# Schematic_16bitCalculator.net
KiCad netlist of a schematic drawn in EasyEDA
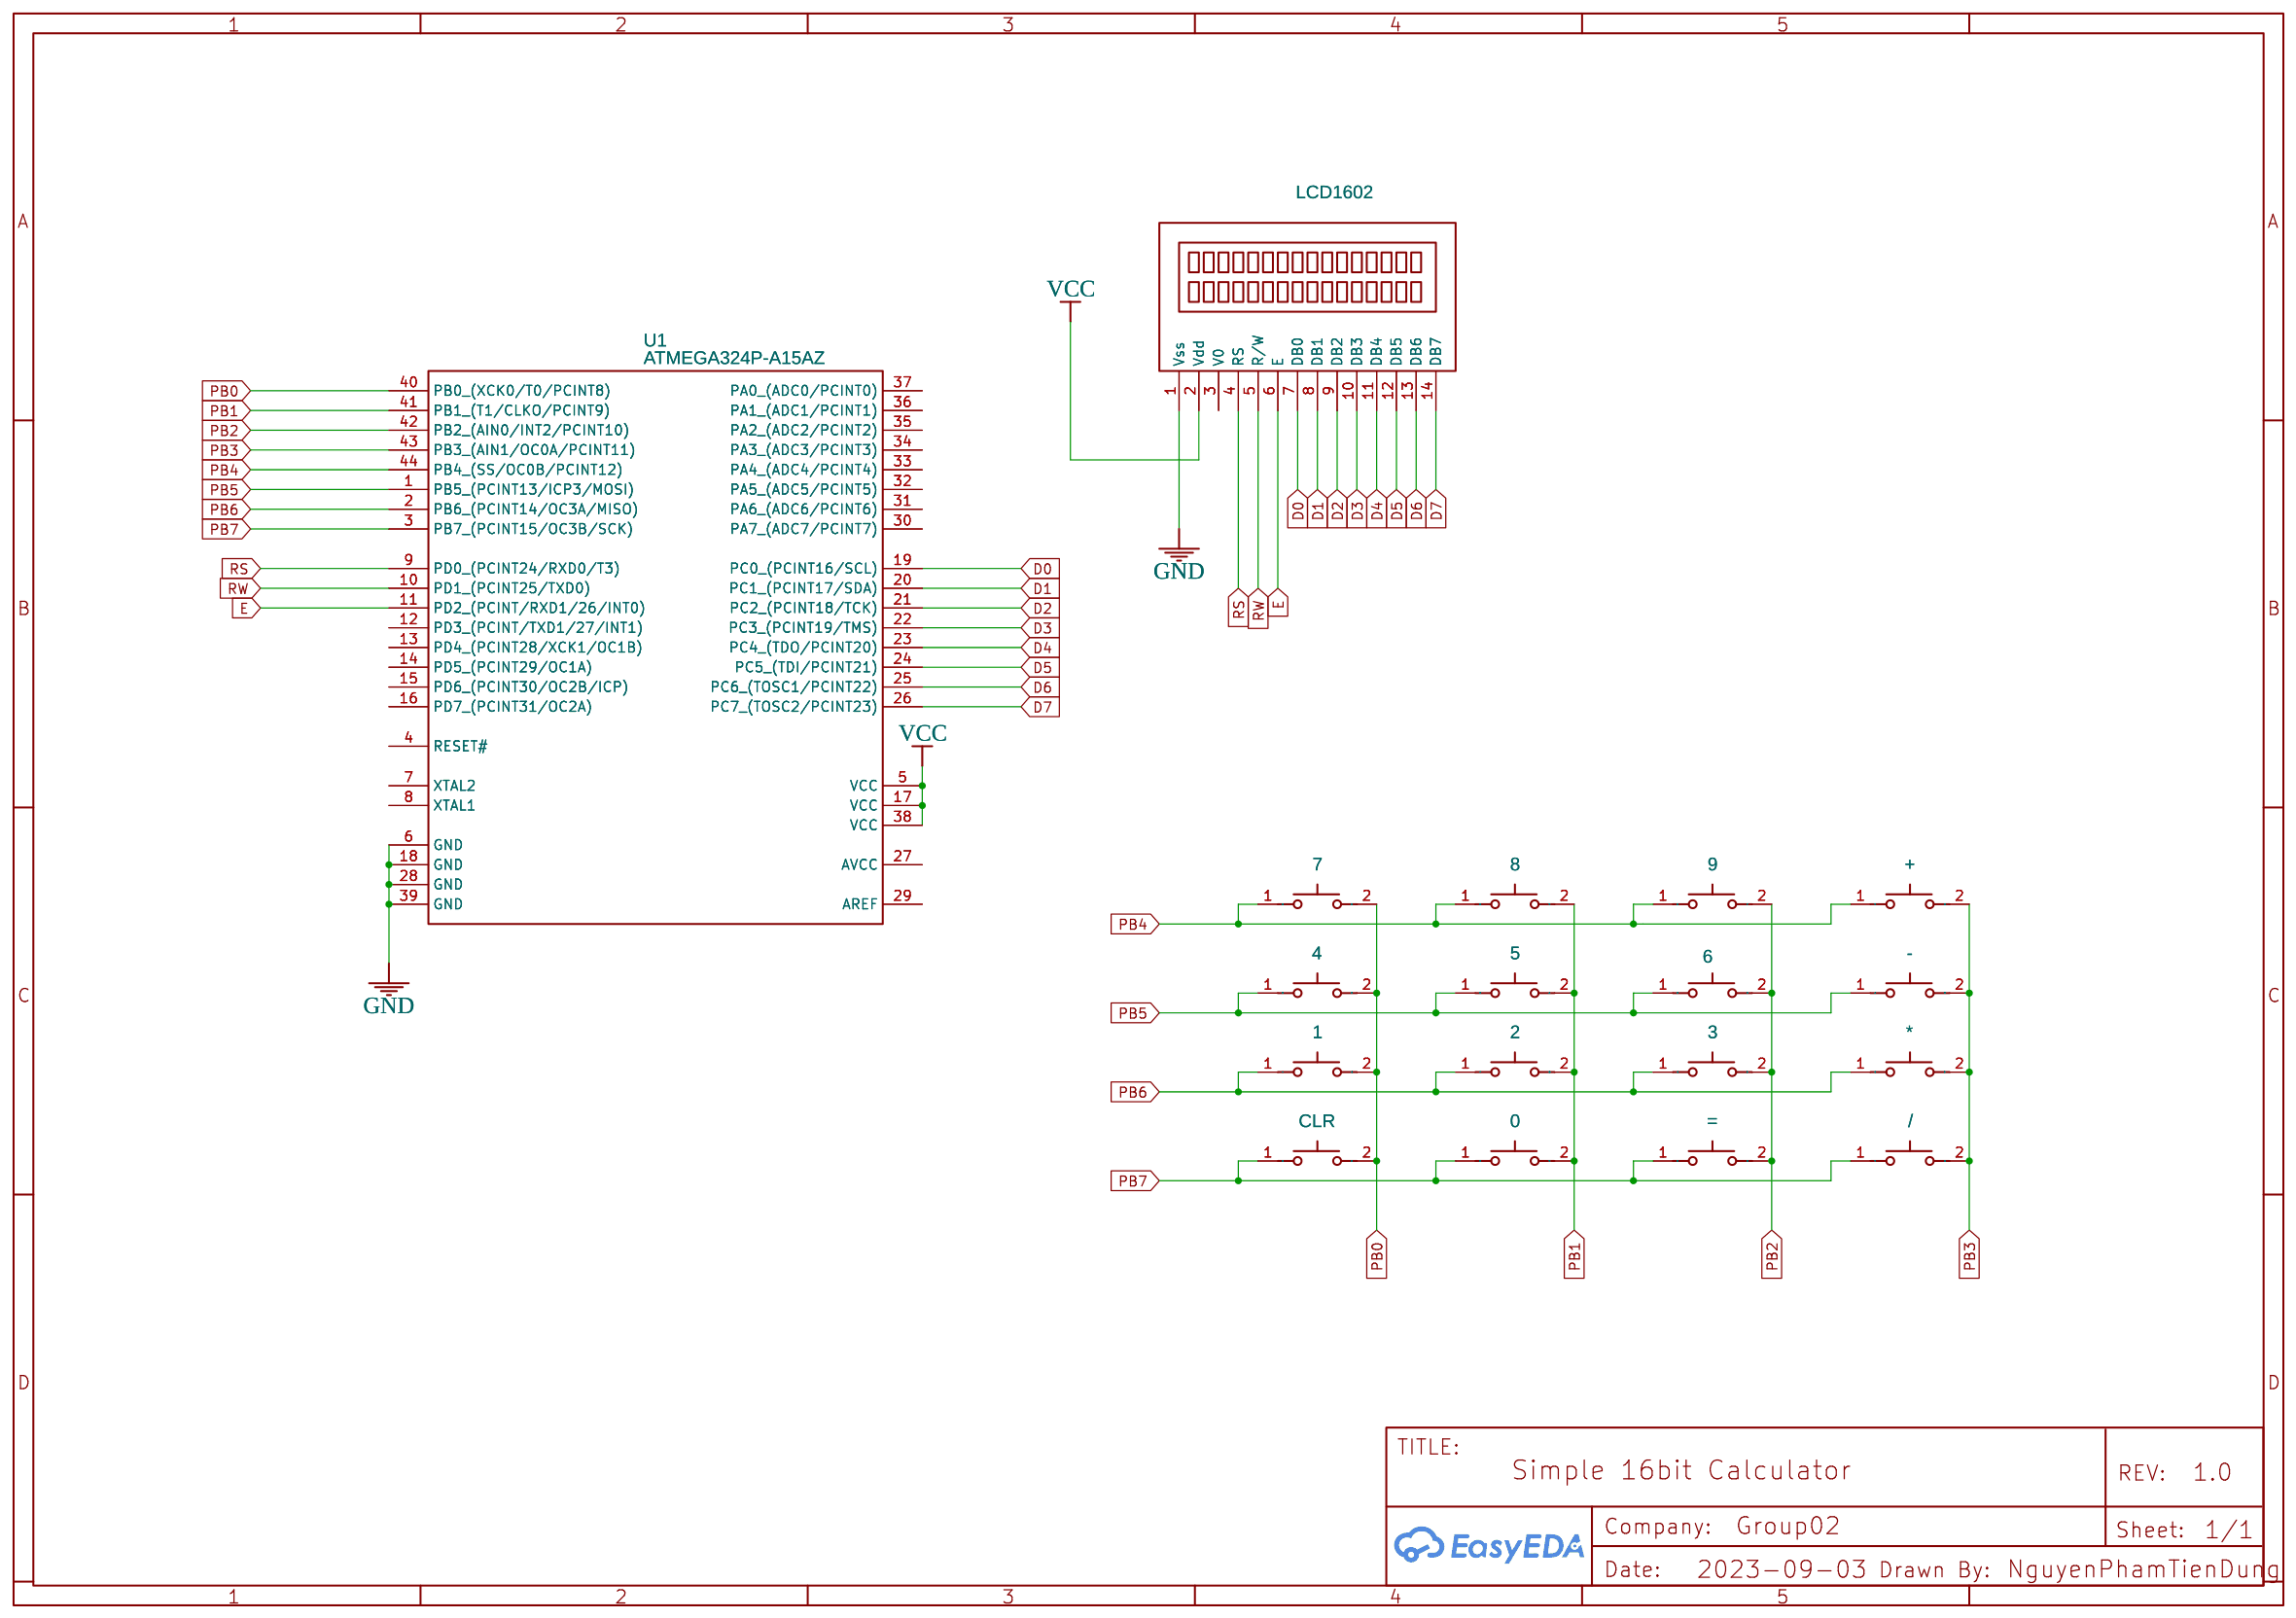
[diagram p0: schematic sheet]

(export (version "E")
  (design (tool "Eeschema 10.0.6"))
  (components
    (comp (ref "*") (value "BUTTON2") (libsource (lib "") (part "BUTTON2_5")))
    (comp (ref "+") (value "BUTTON2") (libsource (lib "") (part "BUTTON2_3")))
    (comp (ref "-") (value "BUTTON2") (libsource (lib "") (part "BUTTON2_6")))
    (comp (ref "/") (value "BUTTON2") (libsource (lib "") (part "BUTTON2_1")))
    (comp (ref "0") (value "BUTTON2") (libsource (lib "") (part "BUTTON2")))
    (comp (ref "1") (value "BUTTON2") (libsource (lib "") (part "BUTTON2")))
    (comp (ref "2") (value "BUTTON2") (libsource (lib "") (part "BUTTON2")))
    (comp (ref "3") (value "BUTTON2") (libsource (lib "") (part "BUTTON2")))
    (comp (ref "4") (value "BUTTON2") (libsource (lib "") (part "BUTTON2")))
    (comp (ref "5") (value "BUTTON2") (libsource (lib "") (part "BUTTON2")))
    (comp (ref "6") (value "BUTTON2") (libsource (lib "") (part "BUTTON2")))
    (comp (ref "7") (value "BUTTON2") (libsource (lib "") (part "BUTTON2")))
    (comp (ref "8") (value "BUTTON2") (libsource (lib "") (part "BUTTON2")))
    (comp (ref "9") (value "BUTTON2") (libsource (lib "") (part "BUTTON2")))
    (comp (ref "=") (value "BUTTON2") (libsource (lib "") (part "BUTTON2_2")))
    (comp (ref "CLR") (value "BUTTON2") (libsource (lib "") (part "BUTTON2_4")))
    (comp (ref "LCD1602")
      (value "NO")
      (fields (field (name "Manufacturer Part") "LCD LM016L 16x2"))
      (libsource (lib "") (part "LM016L"))
    )
    (comp (ref "U1")
      (value "ATMEGA324P-A15AZ")
      (fields (field (name "Manufacturer") "Atmel"))
      (libsource (lib "") (part "ATMEGA324P-A15AZ"))
    )
  )
  (nets
    (net (code "1") (name "D0") (class "Default")
      (node (ref "LCD1602") (pin "7") (pinfunction "DB0_7") (pintype "unspecified"))
      (node (ref "U1") (pin "19") (pinfunction "PC0_(PCINT16/SCL)_19") (pintype "bidirectional"))
    )
    (net (code "2") (name "D1") (class "Default")
      (node (ref "LCD1602") (pin "8") (pinfunction "DB1_8") (pintype "unspecified"))
      (node (ref "U1") (pin "20") (pinfunction "PC1_(PCINT17/SDA)_20") (pintype "bidirectional"))
    )
    (net (code "3") (name "D2") (class "Default")
      (node (ref "LCD1602") (pin "9") (pinfunction "DB2_9") (pintype "unspecified"))
      (node (ref "U1") (pin "21") (pinfunction "PC2_(PCINT18/TCK)_21") (pintype "bidirectional"))
    )
    (net (code "4") (name "D3") (class "Default")
      (node (ref "LCD1602") (pin "10") (pinfunction "DB3_10") (pintype "unspecified"))
      (node (ref "U1") (pin "22") (pinfunction "PC3_(PCINT19/TMS)_22") (pintype "bidirectional"))
    )
    (net (code "5") (name "D4") (class "Default")
      (node (ref "LCD1602") (pin "11") (pinfunction "DB4_11") (pintype "unspecified"))
      (node (ref "U1") (pin "23") (pinfunction "PC4_(TDO/PCINT20)_23") (pintype "bidirectional"))
    )
    (net (code "6") (name "D5") (class "Default")
      (node (ref "LCD1602") (pin "12") (pinfunction "DB5_12") (pintype "unspecified"))
      (node (ref "U1") (pin "24") (pinfunction "PC5_(TDI/PCINT21)_24") (pintype "bidirectional"))
    )
    (net (code "7") (name "D6") (class "Default")
      (node (ref "LCD1602") (pin "13") (pinfunction "DB6_13") (pintype "unspecified"))
      (node (ref "U1") (pin "25") (pinfunction "PC6_(TOSC1/PCINT22)_25") (pintype "bidirectional"))
    )
    (net (code "8") (name "D7") (class "Default")
      (node (ref "LCD1602") (pin "14") (pinfunction "DB7_14") (pintype "unspecified"))
      (node (ref "U1") (pin "26") (pinfunction "PC7_(TOSC2/PCINT23)_26") (pintype "bidirectional"))
    )
    (net (code "9") (name "E") (class "Default")
      (node (ref "LCD1602") (pin "6") (pinfunction "E_6") (pintype "unspecified"))
      (node (ref "U1") (pin "11") (pinfunction "PD2_(PCINT/RXD1/26/INT0)_11") (pintype "bidirectional"))
    )
    (net (code "10") (name "GND") (class "Default")
      (node (ref "LCD1602") (pin "1") (pinfunction "Vss_1") (pintype "unspecified"))
      (node (ref "U1") (pin "18") (pinfunction "GND_18") (pintype "passive"))
      (node (ref "U1") (pin "28") (pinfunction "GND_28") (pintype "passive"))
      (node (ref "U1") (pin "39") (pinfunction "GND_39") (pintype "passive"))
      (node (ref "U1") (pin "6") (pinfunction "GND_6") (pintype "passive"))
    )
    (net (code "11") (name "PB0") (class "Default")
      (node (ref "1") (pin "2") (pinfunction "2_2") (pintype "unspecified"))
      (node (ref "4") (pin "2") (pinfunction "2_2") (pintype "unspecified"))
      (node (ref "7") (pin "2") (pinfunction "2_2") (pintype "unspecified"))
      (node (ref "CLR") (pin "2") (pinfunction "2_2") (pintype "unspecified"))
      (node (ref "U1") (pin "40") (pinfunction "PB0_(XCK0/T0/PCINT8)_40") (pintype "bidirectional"))
    )
    (net (code "12") (name "PB1") (class "Default")
      (node (ref "0") (pin "2") (pinfunction "2_2") (pintype "unspecified"))
      (node (ref "2") (pin "2") (pinfunction "2_2") (pintype "unspecified"))
      (node (ref "5") (pin "2") (pinfunction "2_2") (pintype "unspecified"))
      (node (ref "8") (pin "2") (pinfunction "2_2") (pintype "unspecified"))
      (node (ref "U1") (pin "41") (pinfunction "PB1_(T1/CLKO/PCINT9)_41") (pintype "bidirectional"))
    )
    (net (code "13") (name "PB2") (class "Default")
      (node (ref "3") (pin "2") (pinfunction "2_2") (pintype "unspecified"))
      (node (ref "6") (pin "2") (pinfunction "2_2") (pintype "unspecified"))
      (node (ref "9") (pin "2") (pinfunction "2_2") (pintype "unspecified"))
      (node (ref "=") (pin "2") (pinfunction "2_2") (pintype "unspecified"))
      (node (ref "U1") (pin "42") (pinfunction "PB2_(AIN0/INT2/PCINT10)_42") (pintype "bidirectional"))
    )
    (net (code "14") (name "PB3") (class "Default")
      (node (ref "*") (pin "2") (pinfunction "2_2") (pintype "unspecified"))
      (node (ref "+") (pin "2") (pinfunction "2_2") (pintype "unspecified"))
      (node (ref "-") (pin "2") (pinfunction "2_2") (pintype "unspecified"))
      (node (ref "/") (pin "2") (pinfunction "2_2") (pintype "unspecified"))
      (node (ref "U1") (pin "43") (pinfunction "PB3_(AIN1/OC0A/PCINT11)_43") (pintype "bidirectional"))
    )
    (net (code "15") (name "PB4") (class "Default")
      (node (ref "+") (pin "1") (pinfunction "1_1") (pintype "unspecified"))
      (node (ref "7") (pin "1") (pinfunction "1_1") (pintype "unspecified"))
      (node (ref "8") (pin "1") (pinfunction "1_1") (pintype "unspecified"))
      (node (ref "9") (pin "1") (pinfunction "1_1") (pintype "unspecified"))
      (node (ref "U1") (pin "44") (pinfunction "PB4_(SS/OC0B/PCINT12)_44") (pintype "bidirectional"))
    )
    (net (code "16") (name "PB5") (class "Default")
      (node (ref "-") (pin "1") (pinfunction "1_1") (pintype "unspecified"))
      (node (ref "4") (pin "1") (pinfunction "1_1") (pintype "unspecified"))
      (node (ref "5") (pin "1") (pinfunction "1_1") (pintype "unspecified"))
      (node (ref "6") (pin "1") (pinfunction "1_1") (pintype "unspecified"))
      (node (ref "U1") (pin "1") (pinfunction "PB5_(PCINT13/ICP3/MOSI)_1") (pintype "bidirectional"))
    )
    (net (code "17") (name "PB6") (class "Default")
      (node (ref "*") (pin "1") (pinfunction "1_1") (pintype "unspecified"))
      (node (ref "1") (pin "1") (pinfunction "1_1") (pintype "unspecified"))
      (node (ref "2") (pin "1") (pinfunction "1_1") (pintype "unspecified"))
      (node (ref "3") (pin "1") (pinfunction "1_1") (pintype "unspecified"))
      (node (ref "U1") (pin "2") (pinfunction "PB6_(PCINT14/OC3A/MISO)_2") (pintype "bidirectional"))
    )
    (net (code "18") (name "PB7") (class "Default")
      (node (ref "/") (pin "1") (pinfunction "1_1") (pintype "unspecified"))
      (node (ref "0") (pin "1") (pinfunction "1_1") (pintype "unspecified"))
      (node (ref "=") (pin "1") (pinfunction "1_1") (pintype "unspecified"))
      (node (ref "CLR") (pin "1") (pinfunction "1_1") (pintype "unspecified"))
      (node (ref "U1") (pin "3") (pinfunction "PB7_(PCINT15/OC3B/SCK)_3") (pintype "bidirectional"))
    )
    (net (code "19") (name "RS") (class "Default")
      (node (ref "LCD1602") (pin "4") (pinfunction "RS_4") (pintype "unspecified"))
      (node (ref "U1") (pin "9") (pinfunction "PD0_(PCINT24/RXD0/T3)_9") (pintype "bidirectional"))
    )
    (net (code "20") (name "RW") (class "Default")
      (node (ref "LCD1602") (pin "5") (pinfunction "R/W_5") (pintype "unspecified"))
      (node (ref "U1") (pin "10") (pinfunction "PD1_(PCINT25/TXD0)_10") (pintype "bidirectional"))
    )
    (net (code "21") (name "VCC") (class "Default")
      (node (ref "LCD1602") (pin "2") (pinfunction "Vdd_2") (pintype "unspecified"))
      (node (ref "U1") (pin "17") (pinfunction "VCC_17") (pintype "passive"))
      (node (ref "U1") (pin "38") (pinfunction "VCC_38") (pintype "passive"))
      (node (ref "U1") (pin "5") (pinfunction "VCC_5") (pintype "passive"))
    )
    (net (code "22") (name "unconnected-(LCD1602-V0-Pad3)") (class "Default")
      (node (ref "LCD1602") (pin "3") (pinfunction "V0_3") (pintype "unspecified"))
    )
    (net (code "23") (name "unconnected-(U1-AREF-Pad29)") (class "Default")
      (node (ref "U1") (pin "29") (pinfunction "AREF_29") (pintype "passive"))
    )
    (net (code "24") (name "unconnected-(U1-AVCC-Pad27)") (class "Default")
      (node (ref "U1") (pin "27") (pinfunction "AVCC_27") (pintype "passive"))
    )
    (net (code "25") (name "unconnected-(U1-PA0_(ADC0{slash}PCINT0)-Pad37)") (class "Default")
      (node (ref "U1") (pin "37") (pinfunction "PA0_(ADC0/PCINT0)_37") (pintype "bidirectional"))
    )
    (net (code "26") (name "unconnected-(U1-PA1_(ADC1{slash}PCINT1)-Pad36)") (class "Default")
      (node (ref "U1") (pin "36") (pinfunction "PA1_(ADC1/PCINT1)_36") (pintype "bidirectional"))
    )
    (net (code "27") (name "unconnected-(U1-PA2_(ADC2{slash}PCINT2)-Pad35)") (class "Default")
      (node (ref "U1") (pin "35") (pinfunction "PA2_(ADC2/PCINT2)_35") (pintype "bidirectional"))
    )
    (net (code "28") (name "unconnected-(U1-PA3_(ADC3{slash}PCINT3)-Pad34)") (class "Default")
      (node (ref "U1") (pin "34") (pinfunction "PA3_(ADC3/PCINT3)_34") (pintype "bidirectional"))
    )
    (net (code "29") (name "unconnected-(U1-PA4_(ADC4{slash}PCINT4)-Pad33)") (class "Default")
      (node (ref "U1") (pin "33") (pinfunction "PA4_(ADC4/PCINT4)_33") (pintype "bidirectional"))
    )
    (net (code "30") (name "unconnected-(U1-PA5_(ADC5{slash}PCINT5)-Pad32)") (class "Default")
      (node (ref "U1") (pin "32") (pinfunction "PA5_(ADC5/PCINT5)_32") (pintype "bidirectional"))
    )
    (net (code "31") (name "unconnected-(U1-PA6_(ADC6{slash}PCINT6)-Pad31)") (class "Default")
      (node (ref "U1") (pin "31") (pinfunction "PA6_(ADC6/PCINT6)_31") (pintype "bidirectional"))
    )
    (net (code "32") (name "unconnected-(U1-PA7_(ADC7{slash}PCINT7)-Pad30)") (class "Default")
      (node (ref "U1") (pin "30") (pinfunction "PA7_(ADC7/PCINT7)_30") (pintype "bidirectional"))
    )
    (net (code "33") (name "unconnected-(U1-PD3_(PCINT{slash}TXD1{slash}27{slash}INT1)-Pad12)") (class "Default")
      (node (ref "U1") (pin "12") (pinfunction "PD3_(PCINT/TXD1/27/INT1)_12") (pintype "bidirectional"))
    )
    (net (code "34") (name "unconnected-(U1-PD4_(PCINT28{slash}XCK1{slash}OC1B)-Pad13)") (class "Default")
      (node (ref "U1") (pin "13") (pinfunction "PD4_(PCINT28/XCK1/OC1B)_13") (pintype "bidirectional"))
    )
    (net (code "35") (name "unconnected-(U1-PD5_(PCINT29{slash}OC1A)-Pad14)") (class "Default")
      (node (ref "U1") (pin "14") (pinfunction "PD5_(PCINT29/OC1A)_14") (pintype "bidirectional"))
    )
    (net (code "36") (name "unconnected-(U1-PD6_(PCINT30{slash}OC2B{slash}ICP)-Pad15)") (class "Default")
      (node (ref "U1") (pin "15") (pinfunction "PD6_(PCINT30/OC2B/ICP)_15") (pintype "bidirectional"))
    )
    (net (code "37") (name "unconnected-(U1-PD7_(PCINT31{slash}OC2A)-Pad16)") (class "Default")
      (node (ref "U1") (pin "16") (pinfunction "PD7_(PCINT31/OC2A)_16") (pintype "bidirectional"))
    )
    (net (code "38") (name "unconnected-(U1-RESET#-Pad4)") (class "Default")
      (node (ref "U1") (pin "4") (pinfunction "RESET#_4") (pintype "input"))
    )
    (net (code "39") (name "unconnected-(U1-XTAL1-Pad8)") (class "Default")
      (node (ref "U1") (pin "8") (pinfunction "XTAL1_8") (pintype "unspecified"))
    )
    (net (code "40") (name "unconnected-(U1-XTAL2-Pad7)") (class "Default")
      (node (ref "U1") (pin "7") (pinfunction "XTAL2_7") (pintype "unspecified"))
    )
  )
)
